# 4040-PY1598-V9_0.net
KiCad netlist of a schematic drawn in Altium Designer
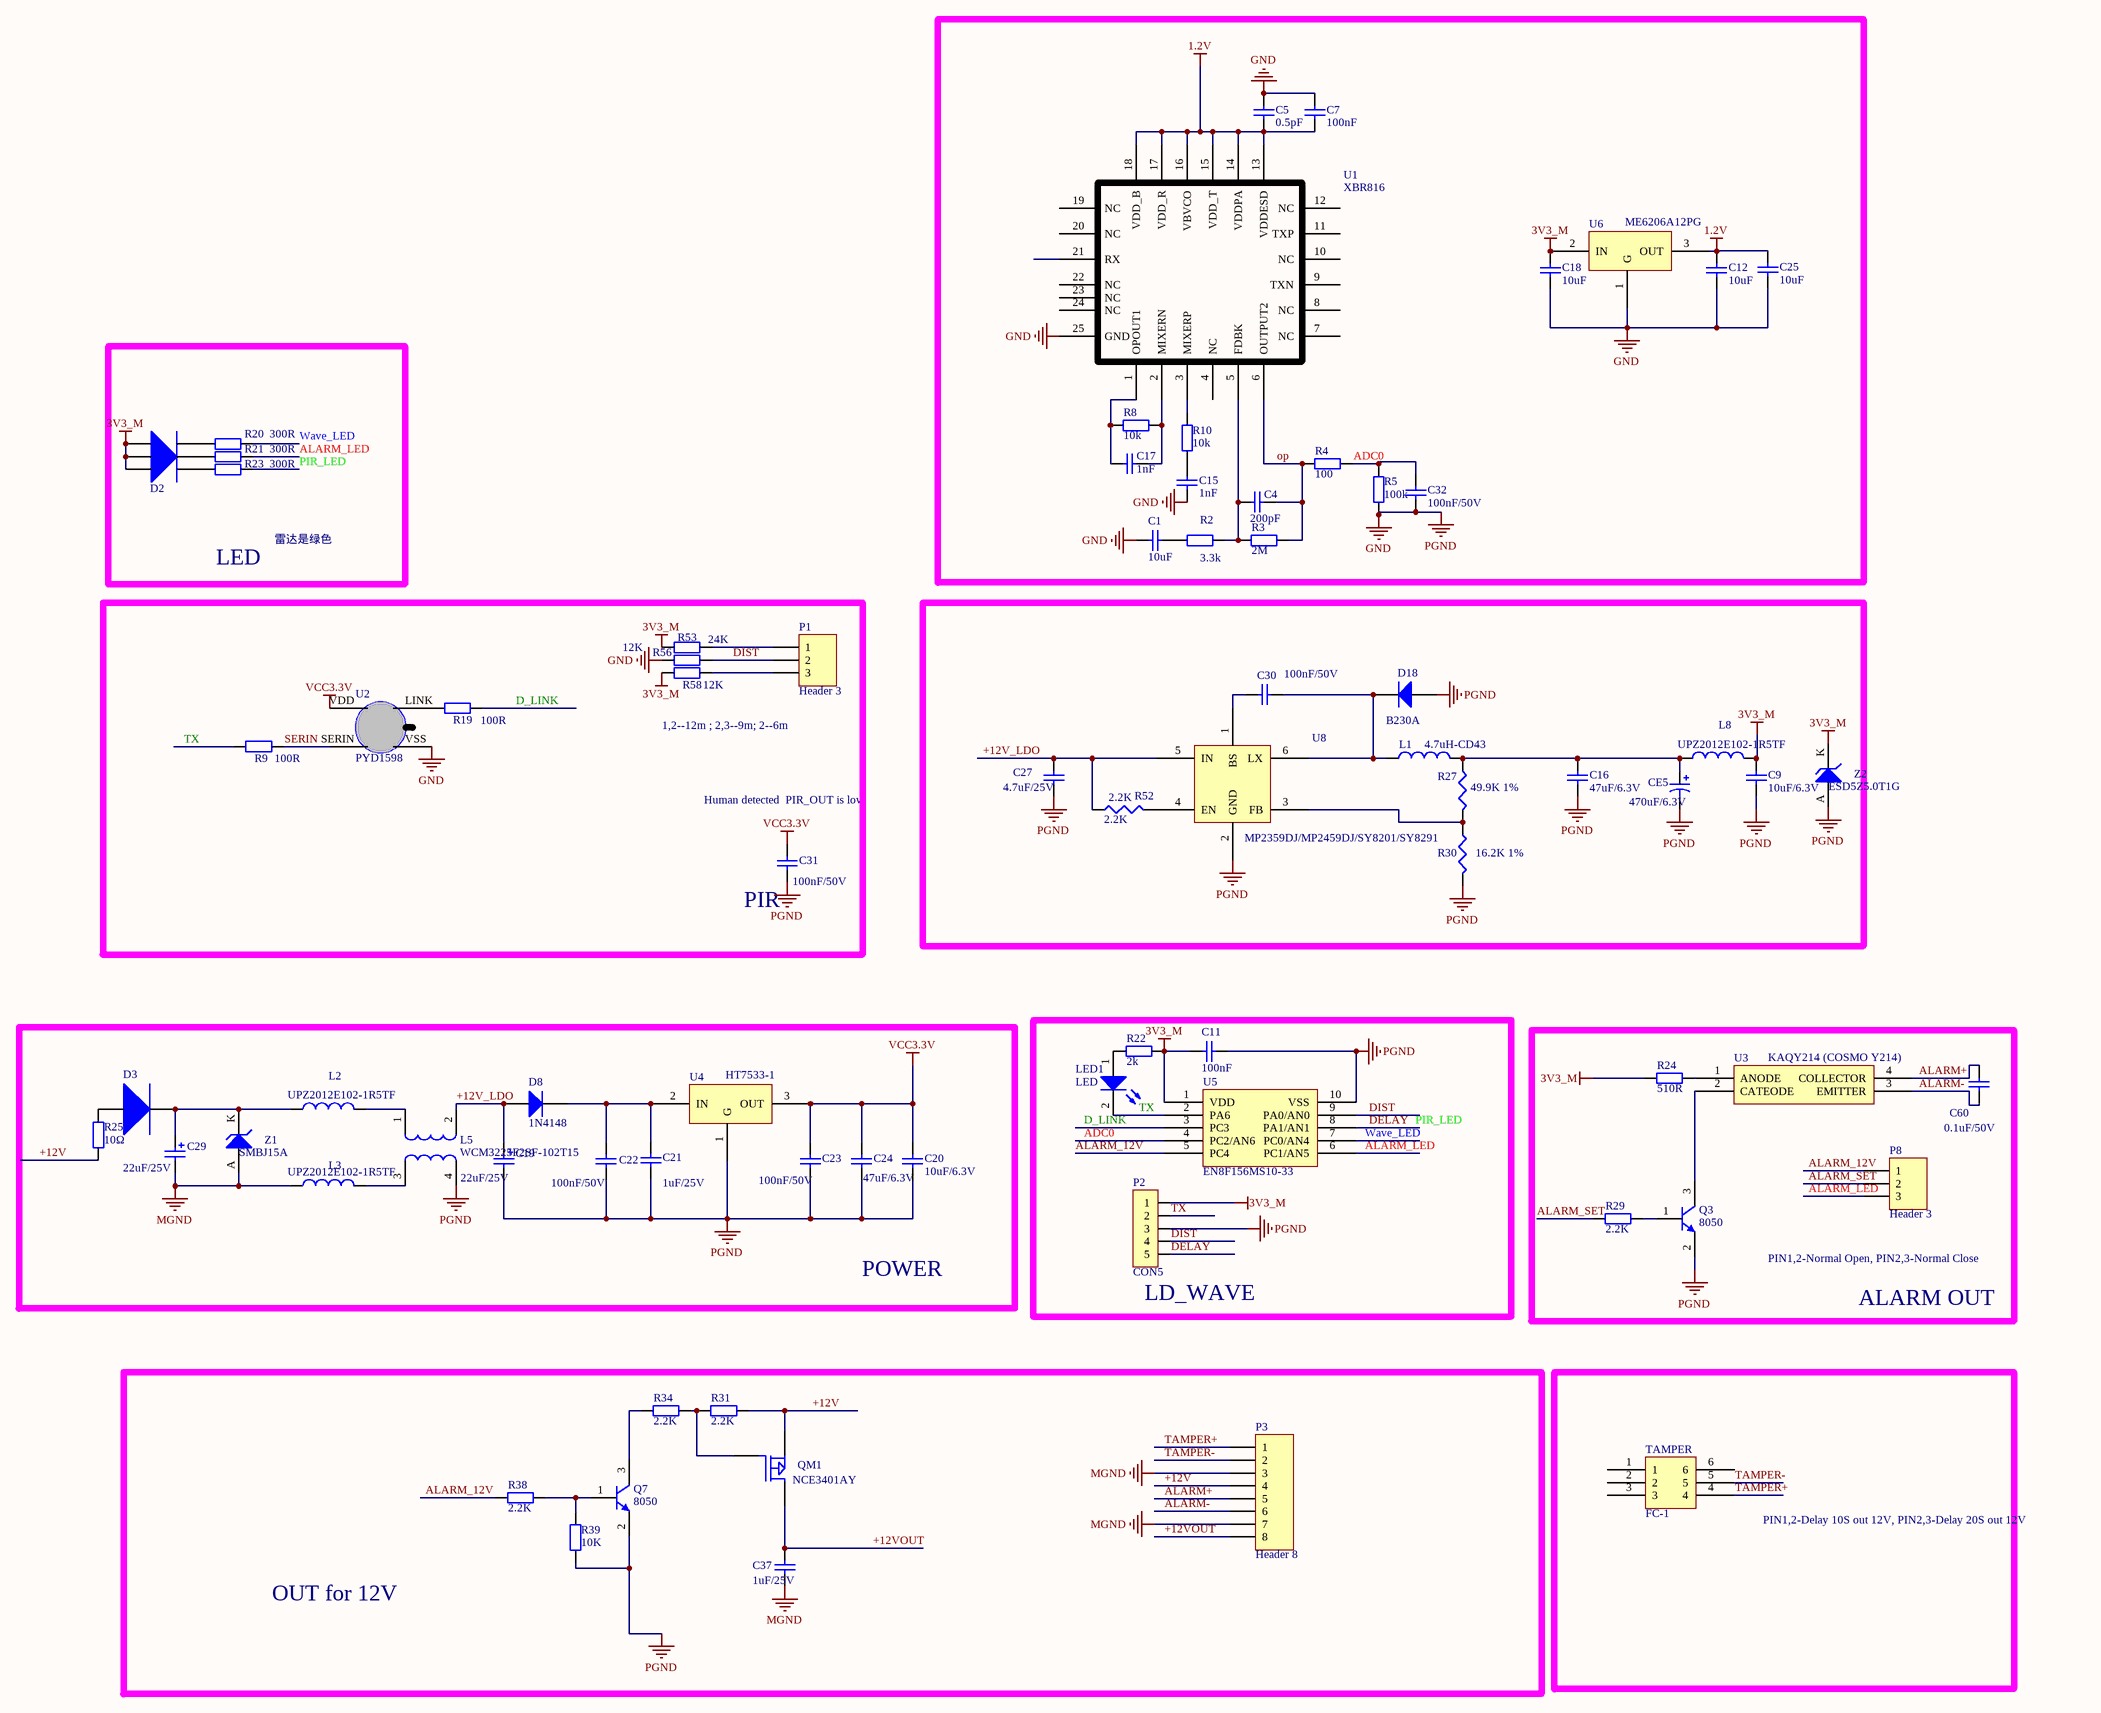
[diagram p0: 微波红外报警探测4040-PY1598-V9.0.SCHDOC]

(export (version "E")
  (design (tool "Eeschema 10.0.6"))
  (components
    (comp (ref "C1")
      (value "10uF")
      (footprint "C0603")
      (description "Capacitor")
      (fields (field (name "PUBLISHER") "Altium Limited"))
      (libsource (lib "Miscellaneous Devices") (part "Cap"))
    )
    (comp (ref "C4")
      (value "200pF")
      (footprint "C0603")
      (description "Capacitor")
      (fields (field (name "PUBLISHER") "Altium Limited"))
      (libsource (lib "Miscellaneous Devices") (part "Cap"))
    )
    (comp (ref "C5")
      (value "0.5pF")
      (footprint "C0603")
      (description "Capacitor")
      (fields (field (name "PUBLISHER") "Altium Limited"))
      (libsource (lib "Miscellaneous Devices") (part "Cap"))
    )
    (comp (ref "C7")
      (value "100nF")
      (footprint "C0603")
      (description "Capacitor")
      (fields (field (name "PUBLISHER") "Altium Limited"))
      (libsource (lib "Miscellaneous Devices") (part "Cap"))
    )
    (comp (ref "C9")
      (value "10uF/6.3V")
      (footprint "C0603")
      (description "Capacitor")
      (fields (field (name "PUBLISHER") "Altium Limited"))
      (libsource (lib "Miscellaneous Devices") (part "Cap"))
    )
    (comp (ref "C11")
      (value "100nF")
      (footprint "C0603")
      (description "Capacitor")
      (fields (field (name "PUBLISHER") "Altium Limited"))
      (libsource (lib "Miscellaneous Devices") (part "Cap"))
    )
    (comp (ref "C12")
      (value "10uF")
      (footprint "C0603")
      (description "Capacitor")
      (fields (field (name "PUBLISHER") "Altium Limited"))
      (libsource (lib "Miscellaneous Devices") (part "Cap"))
    )
    (comp (ref "C15")
      (value "1nF")
      (footprint "C0603")
      (description "Capacitor")
      (fields (field (name "PUBLISHER") "Altium Limited"))
      (libsource (lib "Miscellaneous Devices") (part "Cap"))
    )
    (comp (ref "C16")
      (value "47uF/6.3V")
      (footprint "0805")
      (description "Capacitor (Semiconductor SIM Model)")
      (fields (field (name "PUBLISHER") "Altium Limited"))
      (libsource (lib "Miscellaneous Devices") (part "Cap Semi"))
    )
    (comp (ref "C17")
      (value "1nF")
      (footprint "C0603")
      (description "Capacitor")
      (fields (field (name "PUBLISHER") "Altium Limited"))
      (libsource (lib "Miscellaneous Devices") (part "Cap"))
    )
    (comp (ref "C18")
      (value "10uF")
      (footprint "C0603")
      (description "Capacitor")
      (fields (field (name "PUBLISHER") "Altium Limited"))
      (libsource (lib "Miscellaneous Devices") (part "Cap"))
    )
    (comp (ref "C19")
      (value "22uF/25V")
      (footprint "CAP5.0X5.4")
      (description "Polarized Capacitor (Axial)")
      (fields (field (name "PUBLISHER") "Altium Limited"))
      (libsource (lib "Miscellaneous Devices") (part "Cap Pol2"))
    )
    (comp (ref "C20")
      (value "10uF/6.3V")
      (footprint "C0603")
      (description "Capacitor")
      (fields (field (name "PUBLISHER") "Altium Limited"))
      (libsource (lib "Miscellaneous Devices") (part "Cap"))
    )
    (comp (ref "C21")
      (value "1uF/25V")
      (footprint "C0805")
      (description "Capacitor")
      (fields (field (name "PUBLISHER") "Altium Limited"))
      (libsource (lib "Miscellaneous Devices") (part "Cap"))
    )
    (comp (ref "C22")
      (value "100nF/50V")
      (footprint "C0603")
      (description "Capacitor")
      (fields (field (name "PUBLISHER") "Altium Limited"))
      (libsource (lib "Miscellaneous Devices") (part "Cap"))
    )
    (comp (ref "C23")
      (value "100nF/50V")
      (footprint "C0603")
      (description "Capacitor")
      (fields (field (name "PUBLISHER") "Altium Limited"))
      (libsource (lib "Miscellaneous Devices") (part "Cap"))
    )
    (comp (ref "C24")
      (value "47uF/6.3V")
      (footprint "C0805")
      (description "Capacitor")
      (fields (field (name "PUBLISHER") "Altium Limited"))
      (libsource (lib "Miscellaneous Devices") (part "Cap"))
    )
    (comp (ref "C25")
      (value "10uF")
      (footprint "C0603")
      (description "Capacitor")
      (fields (field (name "PUBLISHER") "Altium Limited"))
      (libsource (lib "Miscellaneous Devices") (part "Cap"))
    )
    (comp (ref "C27")
      (value "4.7uF/25V")
      (footprint "0805")
      (description "Capacitor (Semiconductor SIM Model)")
      (fields (field (name "PUBLISHER") "Altium Limited"))
      (libsource (lib "Miscellaneous Devices") (part "Cap Semi"))
    )
    (comp (ref "C29")
      (value "22uF/25V")
      (footprint "CAP5.0X5.4")
      (description "Polarized Capacitor (Axial)")
      (fields (field (name "PUBLISHER") "Altium Limited"))
      (libsource (lib "Miscellaneous Devices") (part "Cap Pol2"))
    )
    (comp (ref "C30")
      (value "100nF/50V")
      (footprint "0603")
      (description "Capacitor (Semiconductor SIM Model)")
      (fields (field (name "PUBLISHER") "Altium Limited"))
      (libsource (lib "Miscellaneous Devices") (part "Cap Semi"))
    )
    (comp (ref "C31")
      (value "100nF/50V")
      (footprint "C0603")
      (description "Capacitor")
      (fields (field (name "PUBLISHER") "Altium Limited"))
      (libsource (lib "Miscellaneous Devices") (part "Cap"))
    )
    (comp (ref "C32")
      (value "100nF/50V")
      (footprint "0603")
      (description "Capacitor (Semiconductor SIM Model)")
      (fields (field (name "PUBLISHER") "Altium Limited"))
      (libsource (lib "Miscellaneous Devices") (part "Cap Semi"))
    )
    (comp (ref "C37")
      (value "1uF/25V")
      (footprint "C0805")
      (description "Capacitor")
      (fields (field (name "PUBLISHER") "Altium Limited"))
      (libsource (lib "Miscellaneous Devices") (part "Cap"))
    )
    (comp (ref "C60")
      (value "0.1uF/50V")
      (footprint "C0805")
      (description "Capacitor")
      (fields (field (name "PUBLISHER") "Altium Limited"))
      (libsource (lib "Miscellaneous Devices") (part "Cap"))
    )
    (comp (ref "CE5")
      (value "470uF/6.3V")
      (footprint "CAP6.3X5.4")
      (description "Polarized Capacitor (Radial)")
      (fields (field (name "PUBLISHER") "Altium Limited"))
      (libsource (lib "Miscellaneous Devices") (part "Cap Pol1"))
    )
    (comp (ref "D2") (value "led三色共阴极灯") (footprint "三色灯") (libsource (lib "微波红外双鉴电路") (part "led三色共阴极灯")))
    (comp (ref "D3") (value "SS14") (footprint "SS14") (libsource (lib "微波红外双鉴电路") (part "SS14")))
    (comp (ref "D8")
      (value "1N4148")
      (footprint "SOD-80")
      (description "1 Amp General Purpose Rectifier")
      (fields (field (name "PUBLISHER") "Altium Limited"))
      (libsource (lib "Miscellaneous Devices") (part "Diode 1N4005"))
    )
    (comp (ref "D18")
      (value "B230A")
      (footprint "SMA")
      (description "1 Amp General Purpose Rectifier")
      (fields (field (name "PUBLISHER") "Altium Limited"))
      (libsource (lib "Miscellaneous Devices") (part "Diode 1N4007"))
    )
    (comp (ref "L1")
      (value "4.7uH-CD43")
      (footprint "CDRH3D16")
      (description "Inductor")
      (fields (field (name "PUBLISHER") "Altium Limited"))
      (libsource (lib "") (part "Inductor_1"))
    )
    (comp (ref "L2")
      (value "UPZ2012E102-1R5TF")
      (footprint "R0805")
      (description "Inductor")
      (fields (field (name "PUBLISHER") "Altium Limited"))
      (libsource (lib "Miscellaneous Devices") (part "Inductor"))
    )
    (comp (ref "L3")
      (value "UPZ2012E102-1R5TF")
      (footprint "R0805")
      (description "Inductor")
      (fields (field (name "PUBLISHER") "Altium Limited"))
      (libsource (lib "Miscellaneous Devices") (part "Inductor"))
    )
    (comp (ref "L5")
      (value "WCM3225F2SF-102T15")
      (footprint "CMC-3225")
      (description "Transformer")
      (fields (field (name "PUBLISHER") "Altium Limited"))
      (libsource (lib "Miscellaneous Devices") (part "Trans"))
    )
    (comp (ref "L8")
      (value "UPZ2012E102-1R5TF")
      (footprint "R0805")
      (description "Inductor")
      (fields (field (name "PUBLISHER") "Altium Limited"))
      (libsource (lib "Miscellaneous Devices") (part "Inductor"))
    )
    (comp (ref "LED1")
      (value "LED")
      (footprint "LED-0603")
      (fields (field (name "PUBLISHER") "Altium Limited"))
      (libsource (lib "Miscellaneous Devices") (part "LED0"))
    )
    (comp (ref "P1")
      (value "Header 3")
      (footprint "HDR1X3")
      (description "Header, 3-Pin")
      (fields (field (name "PUBLISHER") "Altium Limited"))
      (libsource (lib "Miscellaneous Connectors") (part "Header 3"))
    )
    (comp (ref "P2")
      (value "CON5")
      (footprint "PH2.0-5P")
      (description "Connector")
      (libsource (lib "*") (part "CON5"))
    )
    (comp (ref "P3")
      (value "Header 8")
      (footprint "5.08dip-8")
      (description "Header, 8-Pin")
      (fields (field (name "PUBLISHER") "Altium Limited"))
      (libsource (lib "Miscellaneous Connectors") (part "Header 8"))
    )
    (comp (ref "P8")
      (value "Header 3")
      (footprint "HDR1X3")
      (description "Header, 3-Pin")
      (fields (field (name "PUBLISHER") "Altium Limited"))
      (libsource (lib "Miscellaneous Connectors") (part "Header 3"))
    )
    (comp (ref "Q3")
      (value "8050")
      (footprint "SOT-23")
      (description "NPN General Purpose Amplifier")
      (fields (field (name "PUBLISHER") "Altium Limited"))
      (libsource (lib "圆形报警器NEW-V2.0") (part "2N3904"))
    )
    (comp (ref "Q7")
      (value "8050")
      (footprint "SOT-23")
      (description "NPN General Purpose Amplifier")
      (fields (field (name "PUBLISHER") "Altium Limited"))
      (libsource (lib "圆形报警器NEW-V2.0") (part "2N3904"))
    )
    (comp (ref "QM1") (value "NCE3401AY") (footprint "SOT-23") (libsource (lib "*") (part "MOSFET P")))
    (comp (ref "R2")
      (value "3.3k")
      (footprint "R0603")
      (description "Resistor")
      (fields (field (name "PUBLISHER") "Altium Limited"))
      (libsource (lib "Miscellaneous Devices") (part "Res2"))
    )
    (comp (ref "R3")
      (value "2M")
      (footprint "R0603")
      (description "Resistor")
      (fields (field (name "PUBLISHER") "Altium Limited"))
      (libsource (lib "") (part "Res2_1"))
    )
    (comp (ref "R4")
      (value "100")
      (footprint "R0603")
      (description "Resistor")
      (fields (field (name "PUBLISHER") "Altium Limited"))
      (libsource (lib "Miscellaneous Devices") (part "Res2"))
    )
    (comp (ref "R5")
      (value "100k")
      (footprint "R0603")
      (description "Resistor")
      (fields (field (name "PUBLISHER") "Altium Limited"))
      (libsource (lib "") (part "Res2_2"))
    )
    (comp (ref "R8")
      (value "10k")
      (footprint "R0603")
      (description "Resistor")
      (fields (field (name "PUBLISHER") "Altium Limited"))
      (libsource (lib "") (part "Res2_1"))
    )
    (comp (ref "R9")
      (value "100R")
      (footprint "R0603")
      (description "Resistor")
      (fields (field (name "PUBLISHER") "Altium Limited"))
      (libsource (lib "*") (part "Res2"))
    )
    (comp (ref "R10")
      (value "10k")
      (footprint "R0603")
      (description "Resistor")
      (fields (field (name "PUBLISHER") "Altium Limited"))
      (libsource (lib "") (part "Res2_2"))
    )
    (comp (ref "R19")
      (value "100R")
      (footprint "R0603")
      (description "Resistor")
      (fields (field (name "PUBLISHER") "Altium Limited"))
      (libsource (lib "*") (part "Res2"))
    )
    (comp (ref "R20")
      (value "300R")
      (footprint "R0603")
      (description "Resistor")
      (fields (field (name "Comment") "Res2") (field (name "PUBLISHER") "Altium Limited"))
      (libsource (lib "") (part "Res2_1"))
    )
    (comp (ref "R21")
      (value "300R")
      (footprint "R0603")
      (description "Resistor")
      (fields (field (name "Comment") "Res2") (field (name "PUBLISHER") "Altium Limited"))
      (libsource (lib "") (part "Res2_1"))
    )
    (comp (ref "R22")
      (value "2k")
      (footprint "R0603")
      (description "Resistor")
      (fields (field (name "Comment") "Res2") (field (name "PUBLISHER") "Altium Limited"))
      (libsource (lib "") (part "Res2_1"))
    )
    (comp (ref "R23")
      (value "300R")
      (footprint "R0603")
      (description "Resistor")
      (fields (field (name "Comment") "Res2") (field (name "PUBLISHER") "Altium Limited"))
      (libsource (lib "") (part "Res2_1"))
    )
    (comp (ref "R24")
      (value "510R")
      (footprint "R0603")
      (description "Resistor")
      (fields (field (name "PUBLISHER") "Altium Limited"))
      (libsource (lib "") (part "Res2_1"))
    )
    (comp (ref "R25")
      (value "10Ω")
      (footprint "R0805")
      (description "Resistor")
      (fields (field (name "PUBLISHER") "Altium Limited"))
      (libsource (lib "") (part "Res2_2"))
    )
    (comp (ref "R27")
      (value "49.9K 1%")
      (footprint "0603")
      (description "Resistor")
      (fields (field (name "PUBLISHER") "Altium Limited"))
      (libsource (lib "Miscellaneous Devices") (part "Res3"))
    )
    (comp (ref "R29")
      (value "2.2K")
      (footprint "R0603")
      (description "Resistor")
      (fields (field (name "PUBLISHER") "Altium Limited"))
      (libsource (lib "Miscellaneous Devices") (part "Res2"))
    )
    (comp (ref "R30")
      (value "16.2K 1%")
      (footprint "0603")
      (description "Resistor")
      (fields (field (name "PUBLISHER") "Altium Limited"))
      (libsource (lib "Miscellaneous Devices") (part "Res3"))
    )
    (comp (ref "R31")
      (value "2.2K")
      (footprint "R0603")
      (description "Resistor")
      (fields (field (name "PUBLISHER") "Altium Limited"))
      (libsource (lib "Miscellaneous Devices") (part "Res2"))
    )
    (comp (ref "R34")
      (value "2.2K")
      (footprint "R0603")
      (description "Resistor")
      (fields (field (name "PUBLISHER") "Altium Limited"))
      (libsource (lib "Miscellaneous Devices") (part "Res2"))
    )
    (comp (ref "R38")
      (value "2.2K")
      (footprint "R0603")
      (description "Resistor")
      (fields (field (name "PUBLISHER") "Altium Limited"))
      (libsource (lib "Miscellaneous Devices") (part "Res2"))
    )
    (comp (ref "R39")
      (value "10K")
      (footprint "R0603")
      (description "Resistor")
      (fields (field (name "PUBLISHER") "Altium Limited"))
      (libsource (lib "") (part "Res2_3"))
    )
    (comp (ref "R52")
      (value "2.2K")
      (footprint "0603")
      (description "Resistor")
      (fields (field (name "ALTIUM_VALUE") "2.2K") (field (name "PUBLISHER") "Altium Limited"))
      (libsource (lib "Miscellaneous Devices") (part "Res3"))
    )
    (comp (ref "R53")
      (value "24K")
      (footprint "R0603")
      (description "Resistor")
      (fields (field (name "PUBLISHER") "Altium Limited"))
      (libsource (lib "*") (part "Res2"))
    )
    (comp (ref "R56")
      (value "12K")
      (footprint "R0603")
      (description "Resistor")
      (fields (field (name "PUBLISHER") "Altium Limited"))
      (libsource (lib "*") (part "Res2"))
    )
    (comp (ref "R58")
      (value "12K")
      (footprint "R0603")
      (description "Resistor")
      (fields (field (name "PUBLISHER") "Altium Limited"))
      (libsource (lib "*") (part "Res2"))
    )
    (comp (ref "TAMPER") (value "FC-1") (footprint "TAMPER") (libsource (lib "安防") (part "FC-1")))
    (comp (ref "U1") (value "XBR816") (footprint "QFN24-1") (libsource (lib "Schlib1") (part "XBR1000_24_1")))
    (comp (ref "U2") (value "PYD1598") (libsource (lib "微波红外报警探测4040-PY1598-V9.0") (part "PYD1598")))
    (comp (ref "U3")
      (value "KAQY214 (COSMO Y214)")
      (footprint "TLP627")
      (fields (field (name "Comment") "TLP627"))
      (libsource (lib "微波红外双鉴电路") (part "TLP627"))
    )
    (comp (ref "U4") (value "HT7533-1") (footprint "SOT-89") (libsource (lib "MYLIB") (part "12S33")))
    (comp (ref "U5")
      (value "EN8F156MS10-33")
      (footprint "My Footprint View:MSOP10-0.5")
      (libsource (lib "Schlib1") (part "EN8F156MS10-33"))
    )
    (comp (ref "U6") (value "ME6206A12PG") (footprint "SOT-89") (libsource (lib "MYLIB") (part "12S33")))
    (comp (ref "U8")
      (value "MP2359DJ/MP2459DJ/SY8201/SY8291")
      (footprint "SOT23-6")
      (libsource (lib "SPECIAL-L-V6.6") (part "SY8120B"))
    )
    (comp (ref "Z1")
      (value "SMBJ15A")
      (footprint "SMB")
      (description "Zener Diode")
      (fields (field (name "PUBLISHER") "Altium Limited"))
      (libsource (lib "Miscellaneous Devices") (part "D Zener"))
    )
    (comp (ref "Z2")
      (value "ESD5Z5.0T1G")
      (footprint "SOD323")
      (description "Zener Diode")
      (fields (field (name "PUBLISHER") "Altium Limited"))
      (libsource (lib "Miscellaneous Devices") (part "D Zener"))
    )
  )
  (nets
    (net (code "1") (name "/+12V") (class "Default")
      (node (ref "P3") (pin "4") (pinfunction "4_4") (pintype "passive"))
      (node (ref "QM1") (pin "2") (pinfunction "S_2") (pintype "passive"))
      (node (ref "R25") (pin "2") (pinfunction "2_2") (pintype "passive"))
      (node (ref "R31") (pin "2") (pinfunction "2_2") (pintype "passive"))
    )
    (net (code "2") (name "/+12VOUT") (class "Default")
      (node (ref "C37") (pin "2") (pinfunction "2_2") (pintype "passive"))
      (node (ref "P3") (pin "8") (pinfunction "8_8") (pintype "passive"))
      (node (ref "QM1") (pin "3") (pinfunction "D_3") (pintype "passive"))
    )
    (net (code "3") (name "/+12V_LDO") (class "Default")
      (node (ref "C19") (pin "1") (pinfunction "1_1") (pintype "passive"))
      (node (ref "C27") (pin "1") (pinfunction "1_1") (pintype "passive"))
      (node (ref "D8") (pin "1") (pinfunction "A_1") (pintype "passive"))
      (node (ref "L5") (pin "2") (pinfunction "2_2") (pintype "passive"))
      (node (ref "R52") (pin "1") (pinfunction "1_1") (pintype "passive"))
      (node (ref "U8") (pin "5") (pinfunction "IN_5") (pintype "passive"))
    )
    (net (code "4") (name "/ADC0") (class "Default")
      (node (ref "C32") (pin "1") (pinfunction "1_1") (pintype "passive"))
      (node (ref "R4") (pin "2") (pinfunction "2_2") (pintype "passive"))
      (node (ref "R5") (pin "1") (pinfunction "1_1") (pintype "passive"))
      (node (ref "U5") (pin "4") (pinfunction "PC2/AN6_4") (pintype "passive"))
    )
    (net (code "5") (name "/ALARM+") (class "Default")
      (node (ref "C60") (pin "2") (pinfunction "2_2") (pintype "passive"))
      (node (ref "P3") (pin "5") (pinfunction "5_5") (pintype "passive"))
      (node (ref "U3") (pin "4") (pinfunction "COLLECTOR_4") (pintype "passive"))
    )
    (net (code "6") (name "/ALARM-") (class "Default")
      (node (ref "C60") (pin "1") (pinfunction "1_1") (pintype "passive"))
      (node (ref "P3") (pin "6") (pinfunction "6_6") (pintype "passive"))
      (node (ref "U3") (pin "3") (pinfunction "EMITTER_3") (pintype "passive"))
    )
    (net (code "7") (name "/ALARM_12V") (class "Default")
      (node (ref "P8") (pin "1") (pinfunction "1_1") (pintype "passive"))
      (node (ref "R38") (pin "1") (pinfunction "1_1") (pintype "passive"))
      (node (ref "U5") (pin "5") (pinfunction "PC4_5") (pintype "passive"))
    )
    (net (code "8") (name "/ALARM_LED") (class "Default")
      (node (ref "P8") (pin "3") (pinfunction "3_3") (pintype "passive"))
      (node (ref "R21") (pin "1") (pinfunction "1_1") (pintype "passive"))
      (node (ref "U5") (pin "6") (pinfunction "PC1/AN5_6") (pintype "passive"))
    )
    (net (code "9") (name "/ALARM_SET") (class "Default")
      (node (ref "P8") (pin "2") (pinfunction "2_2") (pintype "passive"))
      (node (ref "R29") (pin "1") (pinfunction "1_1") (pintype "passive"))
    )
    (net (code "10") (name "/DELAY") (class "Default")
      (node (ref "P2") (pin "5") (pinfunction "5_5") (pintype "passive"))
      (node (ref "R23") (pin "1") (pinfunction "1_1") (pintype "passive"))
      (node (ref "U5") (pin "8") (pinfunction "PA1/AN1_8") (pintype "passive"))
    )
    (net (code "11") (name "/DIST") (class "Default")
      (node (ref "P1") (pin "2") (pinfunction "2_2") (pintype "passive"))
      (node (ref "P2") (pin "4") (pinfunction "4_4") (pintype "passive"))
      (node (ref "R56") (pin "1") (pinfunction "1_1") (pintype "passive"))
      (node (ref "U5") (pin "9") (pinfunction "PA0/AN0_9") (pintype "passive"))
    )
    (net (code "12") (name "/D_LINK") (class "Default")
      (node (ref "R19") (pin "1") (pinfunction "1_1") (pintype "passive"))
      (node (ref "U5") (pin "3") (pinfunction "PC3_3") (pintype "passive"))
    )
    (net (code "13") (name "/SERIN") (class "Default")
      (node (ref "R9") (pin "1") (pinfunction "1_1") (pintype "passive"))
      (node (ref "U2") (pin "SERIN") (pinfunction "SERIN_SERIN") (pintype "passive"))
    )
    (net (code "14") (name "/TAMPER+") (class "Default")
      (node (ref "P3") (pin "1") (pinfunction "1_1") (pintype "passive"))
      (node (ref "TAMPER") (pin "4") (pinfunction "4_4") (pintype "passive"))
    )
    (net (code "15") (name "/TAMPER-") (class "Default")
      (node (ref "P3") (pin "2") (pinfunction "2_2") (pintype "passive"))
      (node (ref "TAMPER") (pin "5") (pinfunction "5_5") (pintype "passive"))
    )
    (net (code "16") (name "/TX") (class "Default")
      (node (ref "LED1") (pin "2") (pinfunction "K_2") (pintype "passive"))
      (node (ref "P2") (pin "2") (pinfunction "2_2") (pintype "passive"))
      (node (ref "R9") (pin "2") (pinfunction "2_2") (pintype "passive"))
      (node (ref "U5") (pin "2") (pinfunction "PA6_2") (pintype "passive"))
    )
    (net (code "17") (name "/Wave_LED") (class "Default")
      (node (ref "R20") (pin "1") (pinfunction "1_1") (pintype "passive"))
      (node (ref "U5") (pin "7") (pinfunction "PC0/AN4_7") (pintype "passive"))
    )
    (net (code "18") (name "/op") (class "Default")
      (node (ref "C4") (pin "1") (pinfunction "1_1") (pintype "passive"))
      (node (ref "R3") (pin "1") (pinfunction "1_1") (pintype "passive"))
      (node (ref "R4") (pin "1") (pinfunction "1_1") (pintype "passive"))
      (node (ref "U1") (pin "6") (pinfunction "OUTPUT2_6") (pintype "passive"))
    )
    (net (code "19") (name "1.2V") (class "Default")
      (node (ref "C12") (pin "1") (pinfunction "1_1") (pintype "passive"))
      (node (ref "C25") (pin "1") (pinfunction "1_1") (pintype "passive"))
      (node (ref "C5") (pin "1") (pinfunction "1_1") (pintype "passive"))
      (node (ref "C7") (pin "1") (pinfunction "1_1") (pintype "passive"))
      (node (ref "U1") (pin "13") (pinfunction "VDDESD_13") (pintype "passive"))
      (node (ref "U1") (pin "14") (pinfunction "VDDPA_14") (pintype "passive"))
      (node (ref "U1") (pin "15") (pinfunction "VDD_T_15") (pintype "passive"))
      (node (ref "U1") (pin "16") (pinfunction "VBVCO_16") (pintype "passive"))
      (node (ref "U1") (pin "17") (pinfunction "VDD_R_17") (pintype "passive"))
      (node (ref "U1") (pin "18") (pinfunction "VDD_B_18") (pintype "passive"))
      (node (ref "U6") (pin "3") (pinfunction "OUT_3") (pintype "passive"))
    )
    (net (code "20") (name "3V3_M") (class "Default")
      (node (ref "C11") (pin "2") (pinfunction "2_2") (pintype "passive"))
      (node (ref "C18") (pin "1") (pinfunction "1_1") (pintype "passive"))
      (node (ref "C9") (pin "1") (pinfunction "1_1") (pintype "passive"))
      (node (ref "D2") (pin "1") (pinfunction "A+_1") (pintype "passive"))
      (node (ref "D2") (pin "2") (pinfunction "B+_2") (pintype "passive"))
      (node (ref "D2") (pin "3") (pinfunction "C+_3") (pintype "passive"))
      (node (ref "L8") (pin "1") (pinfunction "1_1") (pintype "passive"))
      (node (ref "P2") (pin "1") (pinfunction "1_1") (pintype "passive"))
      (node (ref "R22") (pin "1") (pinfunction "1_1") (pintype "passive"))
      (node (ref "R24") (pin "2") (pinfunction "2_2") (pintype "passive"))
      (node (ref "R53") (pin "2") (pinfunction "2_2") (pintype "passive"))
      (node (ref "R58") (pin "2") (pinfunction "2_2") (pintype "passive"))
      (node (ref "U5") (pin "1") (pinfunction "VDD_1") (pintype "passive"))
      (node (ref "U6") (pin "2") (pinfunction "IN_2") (pintype "passive"))
      (node (ref "Z2") (pin "K") (pinfunction "K_K") (pintype "passive"))
    )
    (net (code "21") (name "GND") (class "Default")
      (node (ref "C1") (pin "2") (pinfunction "2_2") (pintype "passive"))
      (node (ref "C11") (pin "1") (pinfunction "1_1") (pintype "passive"))
      (node (ref "C12") (pin "2") (pinfunction "2_2") (pintype "passive"))
      (node (ref "C15") (pin "1") (pinfunction "1_1") (pintype "passive"))
      (node (ref "C16") (pin "2") (pinfunction "2_2") (pintype "passive"))
      (node (ref "C18") (pin "2") (pinfunction "2_2") (pintype "passive"))
      (node (ref "C19") (pin "2") (pinfunction "2_2") (pintype "passive"))
      (node (ref "C20") (pin "2") (pinfunction "2_2") (pintype "passive"))
      (node (ref "C21") (pin "1") (pinfunction "1_1") (pintype "passive"))
      (node (ref "C22") (pin "1") (pinfunction "1_1") (pintype "passive"))
      (node (ref "C23") (pin "1") (pinfunction "1_1") (pintype "passive"))
      (node (ref "C24") (pin "1") (pinfunction "1_1") (pintype "passive"))
      (node (ref "C25") (pin "2") (pinfunction "2_2") (pintype "passive"))
      (node (ref "C27") (pin "2") (pinfunction "2_2") (pintype "passive"))
      (node (ref "C31") (pin "1") (pinfunction "1_1") (pintype "passive"))
      (node (ref "C32") (pin "2") (pinfunction "2_2") (pintype "passive"))
      (node (ref "C5") (pin "2") (pinfunction "2_2") (pintype "passive"))
      (node (ref "C7") (pin "2") (pinfunction "2_2") (pintype "passive"))
      (node (ref "C9") (pin "2") (pinfunction "2_2") (pintype "passive"))
      (node (ref "CE5") (pin "2") (pinfunction "2_2") (pintype "passive"))
      (node (ref "D18") (pin "1") (pinfunction "A_1") (pintype "passive"))
      (node (ref "L5") (pin "4") (pinfunction "4_4") (pintype "passive"))
      (node (ref "P2") (pin "3") (pinfunction "3_3") (pintype "passive"))
      (node (ref "Q3") (pin "2") (pinfunction "E_2") (pintype "passive"))
      (node (ref "Q7") (pin "2") (pinfunction "E_2") (pintype "passive"))
      (node (ref "R30") (pin "2") (pinfunction "2_2") (pintype "passive"))
      (node (ref "R39") (pin "1") (pinfunction "1_1") (pintype "passive"))
      (node (ref "R5") (pin "2") (pinfunction "2_2") (pintype "passive"))
      (node (ref "R56") (pin "2") (pinfunction "2_2") (pintype "passive"))
      (node (ref "U1") (pin "25") (pinfunction "GND_25") (pintype "passive"))
      (node (ref "U2") (pin "VSS") (pinfunction "VSS_VSS") (pintype "passive"))
      (node (ref "U4") (pin "1") (pinfunction "G_1") (pintype "passive"))
      (node (ref "U5") (pin "10") (pinfunction "VSS_10") (pintype "passive"))
      (node (ref "U6") (pin "1") (pinfunction "G_1") (pintype "passive"))
      (node (ref "U8") (pin "2") (pinfunction "GND_2") (pintype "passive"))
      (node (ref "Z2") (pin "A") (pinfunction "A_A") (pintype "passive"))
    )
    (net (code "22") (name "MGND") (class "Default")
      (node (ref "C29") (pin "2") (pinfunction "2_2") (pintype "passive"))
      (node (ref "C37") (pin "1") (pinfunction "1_1") (pintype "passive"))
      (node (ref "L3") (pin "2") (pinfunction "2_2") (pintype "passive"))
      (node (ref "P3") (pin "3") (pinfunction "3_3") (pintype "passive"))
      (node (ref "P3") (pin "7") (pinfunction "7_7") (pintype "passive"))
      (node (ref "Z1") (pin "A") (pinfunction "A_A") (pintype "passive"))
    )
    (net (code "23") (name "Net-(C1-Pad1)") (class "Default")
      (node (ref "C1") (pin "1") (pinfunction "1_1") (pintype "passive"))
      (node (ref "R2") (pin "1") (pinfunction "1_1") (pintype "passive"))
    )
    (net (code "24") (name "Net-(C15-Pad2)") (class "Default")
      (node (ref "C15") (pin "2") (pinfunction "2_2") (pintype "passive"))
      (node (ref "R10") (pin "2") (pinfunction "2_2") (pintype "passive"))
    )
    (net (code "25") (name "Net-(C16-Pad1)") (class "Default")
      (node (ref "C16") (pin "1") (pinfunction "1_1") (pintype "passive"))
      (node (ref "CE5") (pin "1") (pinfunction "1_1") (pintype "passive"))
      (node (ref "L1") (pin "2") (pinfunction "2_2") (pintype "passive"))
      (node (ref "L8") (pin "2") (pinfunction "2_2") (pintype "passive"))
      (node (ref "R27") (pin "1") (pinfunction "1_1") (pintype "passive"))
    )
    (net (code "26") (name "Net-(D2-A-)") (class "Default")
      (node (ref "D2") (pin "4") (pinfunction "A-_4") (pintype "passive"))
      (node (ref "R20") (pin "2") (pinfunction "2_2") (pintype "passive"))
    )
    (net (code "27") (name "Net-(D2-B-)") (class "Default")
      (node (ref "D2") (pin "5") (pinfunction "B-_5") (pintype "passive"))
      (node (ref "R21") (pin "2") (pinfunction "2_2") (pintype "passive"))
    )
    (net (code "28") (name "Net-(D2-C-)") (class "Default")
      (node (ref "D2") (pin "6") (pinfunction "C-_6") (pintype "passive"))
      (node (ref "R23") (pin "2") (pinfunction "2_2") (pintype "passive"))
    )
    (net (code "29") (name "Net-(D3-B)") (class "Default")
      (node (ref "D3") (pin "1") (pinfunction "B_1") (pintype "passive"))
      (node (ref "R25") (pin "1") (pinfunction "1_1") (pintype "passive"))
    )
    (net (code "30") (name "Net-(D3-C)") (class "Default")
      (node (ref "C29") (pin "1") (pinfunction "1_1") (pintype "passive"))
      (node (ref "D3") (pin "2") (pinfunction "C_2") (pintype "passive"))
      (node (ref "L2") (pin "2") (pinfunction "2_2") (pintype "passive"))
      (node (ref "Z1") (pin "K") (pinfunction "K_K") (pintype "passive"))
    )
    (net (code "31") (name "Net-(D8-K)") (class "Default")
      (node (ref "C21") (pin "2") (pinfunction "2_2") (pintype "passive"))
      (node (ref "C22") (pin "2") (pinfunction "2_2") (pintype "passive"))
      (node (ref "D8") (pin "2") (pinfunction "K_2") (pintype "passive"))
      (node (ref "U4") (pin "2") (pinfunction "IN_2") (pintype "passive"))
    )
    (net (code "32") (name "Net-(D18-K)") (class "Default")
      (node (ref "C30") (pin "1") (pinfunction "1_1") (pintype "passive"))
      (node (ref "D18") (pin "2") (pinfunction "K_2") (pintype "passive"))
      (node (ref "L1") (pin "1") (pinfunction "1_1") (pintype "passive"))
      (node (ref "U8") (pin "6") (pinfunction "LX_6") (pintype "passive"))
    )
    (net (code "33") (name "Net-(L2-Pad1)") (class "Default")
      (node (ref "L2") (pin "1") (pinfunction "1_1") (pintype "passive"))
      (node (ref "L5") (pin "1") (pinfunction "1_1") (pintype "passive"))
    )
    (net (code "34") (name "Net-(L3-Pad1)") (class "Default")
      (node (ref "L3") (pin "1") (pinfunction "1_1") (pintype "passive"))
      (node (ref "L5") (pin "3") (pinfunction "3_3") (pintype "passive"))
    )
    (net (code "35") (name "Net-(LED1-A)") (class "Default")
      (node (ref "LED1") (pin "1") (pinfunction "A_1") (pintype "passive"))
      (node (ref "R22") (pin "2") (pinfunction "2_2") (pintype "passive"))
    )
    (net (code "36") (name "Net-(P1-Pad1)") (class "Default")
      (node (ref "P1") (pin "1") (pinfunction "1_1") (pintype "passive"))
      (node (ref "R53") (pin "1") (pinfunction "1_1") (pintype "passive"))
    )
    (net (code "37") (name "Net-(P1-Pad3)") (class "Default")
      (node (ref "P1") (pin "3") (pinfunction "3_3") (pintype "passive"))
      (node (ref "R58") (pin "1") (pinfunction "1_1") (pintype "passive"))
    )
    (net (code "38") (name "Net-(Q3-B)") (class "Default")
      (node (ref "Q3") (pin "1") (pinfunction "B_1") (pintype "passive"))
      (node (ref "R29") (pin "2") (pinfunction "2_2") (pintype "passive"))
    )
    (net (code "39") (name "Net-(Q3-C)") (class "Default")
      (node (ref "Q3") (pin "3") (pinfunction "C_3") (pintype "passive"))
      (node (ref "U3") (pin "2") (pinfunction "CATEODE_2") (pintype "passive"))
    )
    (net (code "40") (name "Net-(Q7-B)") (class "Default")
      (node (ref "Q7") (pin "1") (pinfunction "B_1") (pintype "passive"))
      (node (ref "R38") (pin "2") (pinfunction "2_2") (pintype "passive"))
      (node (ref "R39") (pin "2") (pinfunction "2_2") (pintype "passive"))
    )
    (net (code "41") (name "Net-(Q7-C)") (class "Default")
      (node (ref "Q7") (pin "3") (pinfunction "C_3") (pintype "passive"))
      (node (ref "R34") (pin "1") (pinfunction "1_1") (pintype "passive"))
    )
    (net (code "42") (name "Net-(QM1-G)") (class "Default")
      (node (ref "QM1") (pin "1") (pinfunction "G_1") (pintype "passive"))
      (node (ref "R31") (pin "1") (pinfunction "1_1") (pintype "passive"))
      (node (ref "R34") (pin "2") (pinfunction "2_2") (pintype "passive"))
    )
    (net (code "43") (name "Net-(R19-Pad2)") (class "Default")
      (node (ref "R19") (pin "2") (pinfunction "2_2") (pintype "passive"))
      (node (ref "U2") (pin "LINK") (pinfunction "LINK_LINK") (pintype "passive"))
    )
    (net (code "44") (name "Net-(U1-FDBK)") (class "Default")
      (node (ref "C4") (pin "2") (pinfunction "2_2") (pintype "passive"))
      (node (ref "R2") (pin "2") (pinfunction "2_2") (pintype "passive"))
      (node (ref "R3") (pin "2") (pinfunction "2_2") (pintype "passive"))
      (node (ref "U1") (pin "5") (pinfunction "FDBK_5") (pintype "passive"))
    )
    (net (code "45") (name "Net-(U1-MIXERN)") (class "Default")
      (node (ref "C17") (pin "1") (pinfunction "1_1") (pintype "passive"))
      (node (ref "R8") (pin "1") (pinfunction "1_1") (pintype "passive"))
      (node (ref "U1") (pin "2") (pinfunction "MIXERN_2") (pintype "passive"))
    )
    (net (code "46") (name "Net-(U1-MIXERP)") (class "Default")
      (node (ref "R10") (pin "1") (pinfunction "1_1") (pintype "passive"))
      (node (ref "U1") (pin "3") (pinfunction "MIXERP_3") (pintype "passive"))
    )
    (net (code "47") (name "Net-(U1-OPOUT1)") (class "Default")
      (node (ref "C17") (pin "2") (pinfunction "2_2") (pintype "passive"))
      (node (ref "R8") (pin "2") (pinfunction "2_2") (pintype "passive"))
      (node (ref "U1") (pin "1") (pinfunction "OPOUT1_1") (pintype "passive"))
    )
    (net (code "48") (name "Net-(U3-ANODE)") (class "Default")
      (node (ref "R24") (pin "1") (pinfunction "1_1") (pintype "passive"))
      (node (ref "U3") (pin "1") (pinfunction "ANODE_1") (pintype "passive"))
    )
    (net (code "49") (name "Net-(U8-BS)") (class "Default")
      (node (ref "C30") (pin "2") (pinfunction "2_2") (pintype "passive"))
      (node (ref "U8") (pin "1") (pinfunction "BS_1") (pintype "passive"))
    )
    (net (code "50") (name "Net-(U8-EN)") (class "Default")
      (node (ref "R52") (pin "2") (pinfunction "2_2") (pintype "passive"))
      (node (ref "U8") (pin "4") (pinfunction "EN_4") (pintype "passive"))
    )
    (net (code "51") (name "Net-(U8-FB)") (class "Default")
      (node (ref "R27") (pin "2") (pinfunction "2_2") (pintype "passive"))
      (node (ref "R30") (pin "1") (pinfunction "1_1") (pintype "passive"))
      (node (ref "U8") (pin "3") (pinfunction "FB_3") (pintype "passive"))
    )
    (net (code "52") (name "VCC3.3V") (class "Default")
      (node (ref "C20") (pin "1") (pinfunction "1_1") (pintype "passive"))
      (node (ref "C23") (pin "2") (pinfunction "2_2") (pintype "passive"))
      (node (ref "C24") (pin "2") (pinfunction "2_2") (pintype "passive"))
      (node (ref "C31") (pin "2") (pinfunction "2_2") (pintype "passive"))
      (node (ref "U2") (pin "VDD") (pinfunction "VDD_VDD") (pintype "passive"))
      (node (ref "U4") (pin "3") (pinfunction "OUT_3") (pintype "passive"))
    )
    (net (code "53") (name "unconnected-(TAMPER-Pad1)") (class "Default")
      (node (ref "TAMPER") (pin "1") (pinfunction "1_1") (pintype "passive"))
    )
    (net (code "54") (name "unconnected-(TAMPER-Pad2)") (class "Default")
      (node (ref "TAMPER") (pin "2") (pinfunction "2_2") (pintype "passive"))
    )
    (net (code "55") (name "unconnected-(TAMPER-Pad3)") (class "Default")
      (node (ref "TAMPER") (pin "3") (pinfunction "3_3") (pintype "passive"))
    )
    (net (code "56") (name "unconnected-(TAMPER-Pad6)") (class "Default")
      (node (ref "TAMPER") (pin "6") (pinfunction "6_6") (pintype "passive"))
    )
    (net (code "57") (name "unconnected-(U1-NC-Pad4)") (class "Default")
      (node (ref "U1") (pin "4") (pinfunction "NC_4") (pintype "passive"))
    )
    (net (code "58") (name "unconnected-(U1-NC-Pad7)") (class "Default")
      (node (ref "U1") (pin "7") (pinfunction "NC_7") (pintype "passive"))
    )
    (net (code "59") (name "unconnected-(U1-NC-Pad8)") (class "Default")
      (node (ref "U1") (pin "8") (pinfunction "NC_8") (pintype "passive"))
    )
    (net (code "60") (name "unconnected-(U1-NC-Pad10)") (class "Default")
      (node (ref "U1") (pin "10") (pinfunction "NC_10") (pintype "passive"))
    )
    (net (code "61") (name "unconnected-(U1-NC-Pad12)") (class "Default")
      (node (ref "U1") (pin "12") (pinfunction "NC_12") (pintype "passive"))
    )
    (net (code "62") (name "unconnected-(U1-NC-Pad19)") (class "Default")
      (node (ref "U1") (pin "19") (pinfunction "NC_19") (pintype "passive"))
    )
    (net (code "63") (name "unconnected-(U1-NC-Pad20)") (class "Default")
      (node (ref "U1") (pin "20") (pinfunction "NC_20") (pintype "passive"))
    )
    (net (code "64") (name "unconnected-(U1-NC-Pad22)") (class "Default")
      (node (ref "U1") (pin "22") (pinfunction "NC_22") (pintype "passive"))
    )
    (net (code "65") (name "unconnected-(U1-NC-Pad23)") (class "Default")
      (node (ref "U1") (pin "23") (pinfunction "NC_23") (pintype "passive"))
    )
    (net (code "66") (name "unconnected-(U1-NC-Pad24)") (class "Default")
      (node (ref "U1") (pin "24") (pinfunction "NC_24") (pintype "passive"))
    )
    (net (code "67") (name "unconnected-(U1-RX-Pad21)") (class "Default")
      (node (ref "U1") (pin "21") (pinfunction "RX_21") (pintype "passive"))
    )
    (net (code "68") (name "unconnected-(U1-TXN-Pad9)") (class "Default")
      (node (ref "U1") (pin "9") (pinfunction "TXN_9") (pintype "passive"))
    )
    (net (code "69") (name "unconnected-(U1-TXP-Pad11)") (class "Default")
      (node (ref "U1") (pin "11") (pinfunction "TXP_11") (pintype "passive"))
    )
  )
)
